# LEDs.net
KiCad netlist of a schematic drawn in Altium Designer
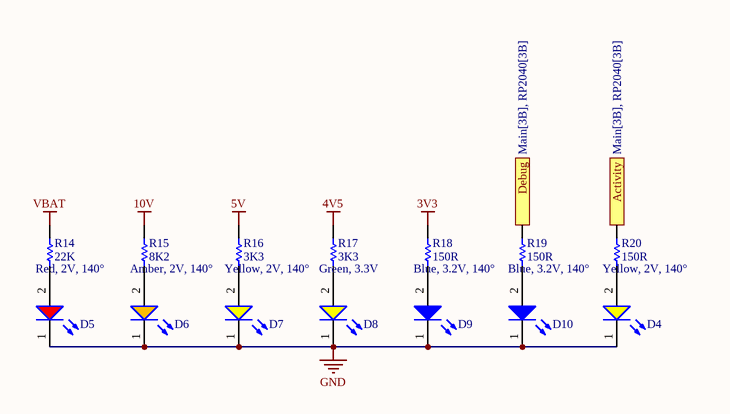
[diagram p0: LEDs.SchDoc]

(export (version "E")
  (design (tool "Eeschema 10.0.6"))
  (components
    (comp (ref "D4")
      (value "Yellow, 2V, 140°")
      (footprint "WL-SMCW_0603_150060xx75000")
      (description "WL-SMCW Mono-color Chip LED Waterclear, size 0603, Yellow, 2V, 140°")
      (fields
        (field (name "MANUFACTURER PART NUMBER") "150060YS75000")
        (field (name "MANUFACTURER") "Wurth Elektronik")
      )
      (libsource (lib "Altium_WL-SMCW (rev22d)") (part "150060YS75000"))
    )
    (comp (ref "D5")
      (value "Red, 2V, 140°")
      (footprint "WL-SMCW_0603_150060xx75000")
      (description "WL-SMCW Mono-color Chip LED Waterclear, size 0603, Red, 2V, 140°")
      (fields
        (field (name "MANUFACTURER PART NUMBER") "150060RS75000")
        (field (name "MANUFACTURER") "Wurth Elektronik")
      )
      (libsource (lib "Altium_WL-SMCW (rev22d)") (part "150060RS75000"))
    )
    (comp (ref "D6")
      (value "Amber, 2V, 140°")
      (footprint "WL-SMCW_0603_150060xx75000")
      (description "WL-SMCW Mono-color Chip LED Waterclear, size 0603, Amber, 2V, 140°")
      (fields
        (field (name "MANUFACTURER PART NUMBER") "150060AS75000")
        (field (name "MANUFACTURER") "Wurth Elektronik")
      )
      (libsource (lib "Altium_WL-SMCW (rev22d)") (part "150060AS75000"))
    )
    (comp (ref "D7")
      (value "Yellow, 2V, 140°")
      (footprint "WL-SMCW_0603_150060xx75000")
      (description "WL-SMCW Mono-color Chip LED Waterclear, size 0603, Yellow, 2V, 140°")
      (fields
        (field (name "MANUFACTURER PART NUMBER") "150060YS75000")
        (field (name "MANUFACTURER") "Wurth Elektronik")
      )
      (libsource (lib "Altium_WL-SMCW (rev22d)") (part "150060YS75000"))
    )
    (comp (ref "D8")
      (value "Green, 3.3V")
      (footprint "WL-SMCW_0603_150060xx75000")
      (description "WL-SMCW Mono-color Chip LED Waterclear, size 0603, Yellow, 2V, 140°")
      (fields
        (field (name "MANUFACTURER PART NUMBER") "150060YS75000")
        (field (name "MANUFACTURER") "Wurth Elektronik")
      )
      (libsource (lib "Altium_WL-SMCW (rev22d)") (part "150060YS75000"))
    )
    (comp (ref "D9")
      (value "Blue, 3.2V, 140°")
      (footprint "WL-SMCW_0603_150060xx75000")
      (description "WL-SMCW Mono-color Chip LED Waterclear, size 0603, Blue, 3.2V, 140°")
      (fields
        (field (name "MANUFACTURER PART NUMBER") "150060BS75000")
        (field (name "MANUFACTURER") "Wurth Elektronik")
      )
      (libsource (lib "Altium_WL-SMCW (rev22d)") (part "150060BS75000"))
    )
    (comp (ref "D10")
      (value "Blue, 3.2V, 140°")
      (footprint "WL-SMCW_0603_150060xx75000")
      (description "WL-SMCW Mono-color Chip LED Waterclear, size 0603, Blue, 3.2V, 140°")
      (fields
        (field (name "MANUFACTURER PART NUMBER") "150060BS75000")
        (field (name "MANUFACTURER") "Wurth Elektronik")
      )
      (libsource (lib "Altium_WL-SMCW (rev22d)") (part "150060BS75000"))
    )
    (comp (ref "R14")
      (value "22K")
      (footprint "RESC0603(1608)_N")
      (description "Chipwiderstand, SMD, Baureihe MC, 1%")
      (fields (field (name "MANUFACTURER") "Multicomp"))
      (libsource (lib "Standardbauteile") (part "Res 22K"))
    )
    (comp (ref "R15")
      (value "8K2")
      (footprint "RESC0603(1608)_N")
      (description "Chipwiderstand, SMD, Baureihe MC, 1%")
      (fields (field (name "MANUFACTURER") "Multicomp"))
      (libsource (lib "Standardbauteile") (part "Res 8K2"))
    )
    (comp (ref "R16")
      (value "3K3")
      (footprint "RESC0603(1608)_N")
      (description "Chipwiderstand, SMD, Baureihe MC, 1%")
      (fields (field (name "MANUFACTURER") "Multicomp"))
      (libsource (lib "Standardbauteile") (part "Res 3K3"))
    )
    (comp (ref "R17")
      (value "3K3")
      (footprint "RESC0603(1608)_N")
      (description "Chipwiderstand, SMD, Baureihe MC, 1%")
      (fields (field (name "MANUFACTURER") "Multicomp"))
      (libsource (lib "Standardbauteile") (part "Res 3K3"))
    )
    (comp (ref "R18")
      (value "150R")
      (footprint "RESC0603(1608)_N")
      (fields (field (name "MANUFACTURER") "Multicomp"))
      (libsource (lib "Standardbauteile") (part "Res 150R"))
    )
    (comp (ref "R19")
      (value "150R")
      (footprint "RESC0603(1608)_N")
      (fields (field (name "MANUFACTURER") "Multicomp"))
      (libsource (lib "Standardbauteile") (part "Res 150R"))
    )
    (comp (ref "R20")
      (value "150R")
      (footprint "RESC0603(1608)_N")
      (fields (field (name "MANUFACTURER") "Multicomp"))
      (libsource (lib "Standardbauteile") (part "Res 150R"))
    )
  )
  (nets
    (net (code "1") (name "/Activity") (class "Default")
      (node (ref "R20") (pin "2") (pinfunction "2_2") (pintype "passive"))
    )
    (net (code "2") (name "/Debug") (class "Default")
      (node (ref "R19") (pin "2") (pinfunction "2_2") (pintype "passive"))
    )
    (net (code "3") (name "3V3") (class "Default")
      (node (ref "R18") (pin "2") (pinfunction "2_2") (pintype "passive"))
    )
    (net (code "4") (name "4V5") (class "Default")
      (node (ref "R17") (pin "2") (pinfunction "2_2") (pintype "passive"))
    )
    (net (code "5") (name "5V") (class "Default")
      (node (ref "R16") (pin "2") (pinfunction "2_2") (pintype "passive"))
    )
    (net (code "6") (name "10V") (class "Default")
      (node (ref "R15") (pin "2") (pinfunction "2_2") (pintype "passive"))
    )
    (net (code "7") (name "GND") (class "Default")
      (node (ref "D10") (pin "1") (pinfunction "K_1") (pintype "passive"))
      (node (ref "D4") (pin "1") (pinfunction "K_1") (pintype "passive"))
      (node (ref "D5") (pin "1") (pinfunction "K_1") (pintype "passive"))
      (node (ref "D6") (pin "1") (pinfunction "K_1") (pintype "passive"))
      (node (ref "D7") (pin "1") (pinfunction "K_1") (pintype "passive"))
      (node (ref "D8") (pin "1") (pinfunction "K_1") (pintype "passive"))
      (node (ref "D9") (pin "1") (pinfunction "K_1") (pintype "passive"))
    )
    (net (code "8") (name "Net-(D4-A)") (class "Default")
      (node (ref "D4") (pin "2") (pinfunction "A_2") (pintype "passive"))
      (node (ref "R20") (pin "1") (pinfunction "1_1") (pintype "passive"))
    )
    (net (code "9") (name "Net-(D5-A)") (class "Default")
      (node (ref "D5") (pin "2") (pinfunction "A_2") (pintype "passive"))
      (node (ref "R14") (pin "1") (pinfunction "1_1") (pintype "passive"))
    )
    (net (code "10") (name "Net-(D6-A)") (class "Default")
      (node (ref "D6") (pin "2") (pinfunction "A_2") (pintype "passive"))
      (node (ref "R15") (pin "1") (pinfunction "1_1") (pintype "passive"))
    )
    (net (code "11") (name "Net-(D7-A)") (class "Default")
      (node (ref "D7") (pin "2") (pinfunction "A_2") (pintype "passive"))
      (node (ref "R16") (pin "1") (pinfunction "1_1") (pintype "passive"))
    )
    (net (code "12") (name "Net-(D8-A)") (class "Default")
      (node (ref "D8") (pin "2") (pinfunction "A_2") (pintype "passive"))
      (node (ref "R17") (pin "1") (pinfunction "1_1") (pintype "passive"))
    )
    (net (code "13") (name "Net-(D9-A)") (class "Default")
      (node (ref "D9") (pin "2") (pinfunction "A_2") (pintype "passive"))
      (node (ref "R18") (pin "1") (pinfunction "1_1") (pintype "passive"))
    )
    (net (code "14") (name "Net-(D10-A)") (class "Default")
      (node (ref "D10") (pin "2") (pinfunction "A_2") (pintype "passive"))
      (node (ref "R19") (pin "1") (pinfunction "1_1") (pintype "passive"))
    )
    (net (code "15") (name "VBAT") (class "Default")
      (node (ref "R14") (pin "2") (pinfunction "2_2") (pintype "passive"))
    )
  )
)
